# TX.net
KiCad netlist of a schematic drawn in Altium Designer
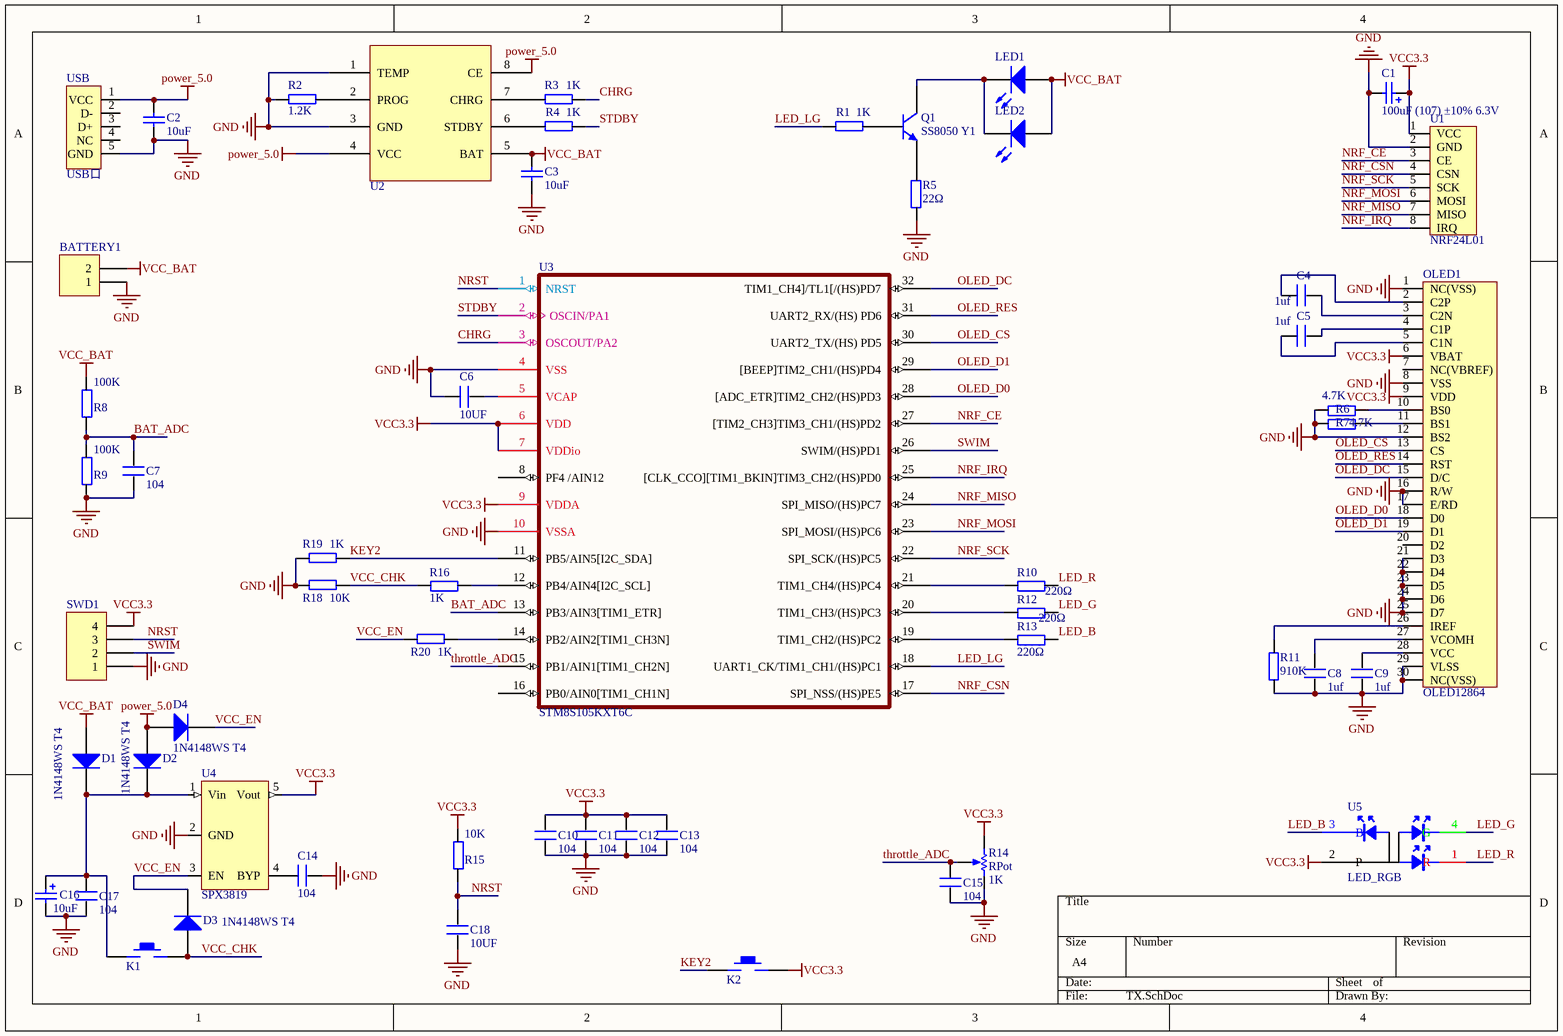
[diagram p0: TX.SchDoc]

(export (version "E")
  (design (tool "Eeschema 10.0.6"))
  (components
    (comp (ref "BATTERY1")
      (value "battery")
      (footprint "HDR1X2")
      (description "Header, 2-Pin")
      (fields (field (name "PUBLISHER") "Altium Limited"))
      (libsource (lib "EXPLORER") (part "Header 2"))
    )
    (comp (ref "C1")
      (value "100uF (107) ±10% 6.3V")
      (footprint "CASE-B_3528")
      (description "钽电容")
      (libsource (lib "Cap") (part "3528 100uF (107) 10% 6.3V"))
    )
    (comp (ref "C2")
      (value "10uF")
      (footprint "1206_C")
      (description "贴片电容")
      (libsource (lib "Cap") (part "1206 10uF (106) 10% 50V"))
    )
    (comp (ref "C3")
      (value "10uF")
      (footprint "1206_C")
      (description "贴片电容")
      (libsource (lib "Cap") (part "1206 10uF (106) 10% 50V"))
    )
    (comp (ref "C4") (value "1uf") (footprint "0603P") (libsource (lib "EXPLORER") (part "C")))
    (comp (ref "C5") (value "1uf") (footprint "0603P") (libsource (lib "EXPLORER") (part "C")))
    (comp (ref "C6") (value "10UF") (footprint "0805") (libsource (lib "EXPLORER") (part "C")))
    (comp (ref "C7") (value "104") (footprint "0603P") (libsource (lib "EXPLORER") (part "C")))
    (comp (ref "C8") (value "1uf") (footprint "0603P") (libsource (lib "EXPLORER") (part "C")))
    (comp (ref "C9") (value "1uf") (footprint "0603P") (libsource (lib "EXPLORER") (part "C")))
    (comp (ref "C10") (value "104") (footprint "0603P") (libsource (lib "EXPLORER") (part "C")))
    (comp (ref "C11") (value "104") (footprint "0603P") (libsource (lib "EXPLORER") (part "C")))
    (comp (ref "C12") (value "104") (footprint "0603P") (libsource (lib "EXPLORER") (part "C")))
    (comp (ref "C13") (value "104") (footprint "0603P") (libsource (lib "EXPLORER") (part "C")))
    (comp (ref "C14") (value "104") (footprint "0603P") (libsource (lib "EXPLORER") (part "C")))
    (comp (ref "C15") (value "104") (footprint "0603P") (libsource (lib "EXPLORER") (part "C")))
    (comp (ref "C16")
      (value "10uF")
      (footprint "CASE-A_3216")
      (description "钽电容")
      (libsource (lib "Cap") (part "3216 10uF (106) 10% 16V"))
    )
    (comp (ref "C17") (value "104") (footprint "0603P") (libsource (lib "EXPLORER") (part "C")))
    (comp (ref "C18") (value "10UF") (footprint "0603P") (libsource (lib "EXPLORER") (part "C")))
    (comp (ref "D1")
      (value "1N4148WS T4")
      (footprint "SOD-323")
      (description "二极管")
      (libsource (lib "Diode") (part "SOD-323 1N4148WS T4"))
    )
    (comp (ref "D2")
      (value "1N4148WS T4")
      (footprint "SOD-323")
      (description "二极管")
      (libsource (lib "Diode") (part "SOD-323 1N4148WS T4"))
    )
    (comp (ref "D3")
      (value "1N4148WS T4")
      (footprint "SOD-323")
      (description "二极管")
      (libsource (lib "Diode") (part "SOD-323 1N4148WS T4"))
    )
    (comp (ref "D4")
      (value "1N4148WS T4")
      (footprint "SOD-323")
      (description "二极管")
      (libsource (lib "Diode") (part "SOD-323 1N4148WS T4"))
    )
    (comp (ref "K1") (value "KEY") (footprint "侧贴按键") (libsource (lib "EXPLORER") (part "KEY_M")))
    (comp (ref "K2") (value "KEY") (footprint "侧贴按键") (libsource (lib "EXPLORER") (part "KEY_M")))
    (comp (ref "LED1")
      (value "LED")
      (footprint "DIODE_3*5.3")
      (description "Typical RED, GREEN, YELLOW, AMBER GaAs LED")
      (fields (field (name "PUBLISHER") "Altium Limited"))
      (libsource (lib "EXPLORER") (part "LED2"))
    )
    (comp (ref "LED2")
      (value "LED")
      (footprint "DIODE_3*5.3")
      (description "Typical RED, GREEN, YELLOW, AMBER GaAs LED")
      (fields (field (name "PUBLISHER") "Altium Limited"))
      (libsource (lib "EXPLORER") (part "LED2"))
    )
    (comp (ref "OLED1")
      (value "OLED12864")
      (footprint "OLED_0.96")
      (libsource (lib "0.96OLED_SCH") (part "OLED12864"))
    )
    (comp (ref "Q1")
      (value "SS8050 Y1")
      (footprint "SOT-23(SOT-23-3)")
      (description "三极管")
      (libsource (lib "Transistor_NPN") (part "SOT-23 SS8050 Y1"))
    )
    (comp (ref "R1") (value "1K") (footprint "0603P") (libsource (lib "*") (part "R")))
    (comp (ref "R2") (value "1.2K") (footprint "0603P") (libsource (lib "*") (part "R")))
    (comp (ref "R3") (value "1K") (footprint "0603P") (libsource (lib "*") (part "R")))
    (comp (ref "R4") (value "1K") (footprint "0603P") (libsource (lib "*") (part "R")))
    (comp (ref "R5") (value "22Ω") (footprint "0603P") (libsource (lib "*") (part "R")))
    (comp (ref "R6") (value "4.7K") (footprint "0603P") (libsource (lib "*") (part "R")))
    (comp (ref "R7") (value "4.7K") (footprint "0603P") (libsource (lib "*") (part "R")))
    (comp (ref "R8") (value "100K") (footprint "0603P") (libsource (lib "*") (part "R")))
    (comp (ref "R9") (value "100K") (footprint "0603P") (libsource (lib "*") (part "R")))
    (comp (ref "R10") (value "220Ω") (footprint "0603P") (libsource (lib "*") (part "R")))
    (comp (ref "R11") (value "910K") (footprint "0603P") (libsource (lib "*") (part "R")))
    (comp (ref "R12") (value "220Ω") (footprint "0603P") (libsource (lib "*") (part "R")))
    (comp (ref "R13") (value "220Ω") (footprint "0603P") (libsource (lib "*") (part "R")))
    (comp (ref "R14")
      (value "RPot")
      (footprint "R_variable")
      (description "Potentiometer")
      (fields (field (name "ALTIUM_VALUE") "1K") (field (name "PUBLISHER") "Altium Limited"))
      (libsource (lib "Miscellaneous Devices") (part "RPot"))
    )
    (comp (ref "R15") (value "10K") (footprint "0603P") (libsource (lib "*") (part "R")))
    (comp (ref "R16") (value "1K") (footprint "0603P") (libsource (lib "*") (part "R")))
    (comp (ref "R18") (value "10K") (footprint "0603P") (libsource (lib "*") (part "R")))
    (comp (ref "R19") (value "1K") (footprint "0603P") (libsource (lib "*") (part "R")))
    (comp (ref "R20") (value "1K") (footprint "0603P") (libsource (lib "*") (part "R")))
    (comp (ref "SWD1")
      (value "SWD")
      (footprint "HDR1X4")
      (description "Header, 4-Pin")
      (fields (field (name "PUBLISHER") "Altium Limited"))
      (libsource (lib "EXPLORER") (part "Header 4"))
    )
    (comp (ref "U1")
      (value "NRF24L01")
      (footprint "miniNRF24L01")
      (libsource (lib "MySchlib") (part "NRF24L01"))
    )
    (comp (ref "U2") (value "TP4056-SOT8") (footprint "SOP-8") (libsource (lib "*") (part "TP4056")))
    (comp (ref "U3")
      (value "STM8S105KXT6C")
      (footprint "TQFP32")
      (description "ST 8-bit  Microcontroller")
      (libsource (lib "STMicrocontroller 8") (part "STM8S105K4T6C"))
    )
    (comp (ref "U4") (value "SPX3819") (footprint "SOT25-5") (libsource (lib "*") (part "SPX3819")))
    (comp (ref "U5")
      (value "LED_RGB")
      (footprint "LED_RGB")
      (description "全彩LED")
      (libsource (lib "*") (part "LED_RGB"))
    )
    (comp (ref "USB") (value "USB口") (footprint "MICRO USB") (libsource (lib "MySchlib") (part "USB口")))
  )
  (nets
    (net (code "1") (name "/BAT_ADC") (class "Default")
      (node (ref "C7") (pin "2") (pintype "passive"))
      (node (ref "R8") (pin "1") (pintype "passive"))
      (node (ref "R9") (pin "2") (pintype "passive"))
      (node (ref "U3") (pin "13") (pinfunction "PB3/AIN3[TIM1_ETR]_13") (pintype "bidirectional"))
    )
    (net (code "2") (name "/CHRG") (class "Default")
      (node (ref "R3") (pin "1") (pintype "passive"))
      (node (ref "U3") (pin "3") (pinfunction "OSCOUT/PA2_3") (pintype "bidirectional"))
    )
    (net (code "3") (name "/KEY2") (class "Default")
      (node (ref "K2") (pin "1") (pinfunction "1_1") (pintype "passive"))
      (node (ref "R19") (pin "1") (pintype "passive"))
      (node (ref "U3") (pin "11") (pinfunction "PB5/AIN5[I2C_SDA]_11") (pintype "bidirectional"))
    )
    (net (code "4") (name "/LED_B") (class "Default")
      (node (ref "R13") (pin "2") (pintype "passive"))
      (node (ref "U5") (pin "3") (pinfunction "B_3") (pintype "passive"))
    )
    (net (code "5") (name "/LED_G") (class "Default")
      (node (ref "R12") (pin "2") (pintype "passive"))
      (node (ref "U5") (pin "4") (pinfunction "G_4") (pintype "passive"))
    )
    (net (code "6") (name "/LED_LG") (class "Default")
      (node (ref "R1") (pin "2") (pintype "passive"))
      (node (ref "U3") (pin "18") (pinfunction "UART1_CK/TIM1_CH1/(HS)PC1_18") (pintype "bidirectional"))
    )
    (net (code "7") (name "/LED_R") (class "Default")
      (node (ref "R10") (pin "2") (pintype "passive"))
      (node (ref "U5") (pin "1") (pinfunction "R_1") (pintype "passive"))
    )
    (net (code "8") (name "/NRF_CE") (class "Default")
      (node (ref "U1") (pin "3") (pinfunction "CE_3") (pintype "passive"))
      (node (ref "U3") (pin "27") (pinfunction "[TIM2_CH3]TIM3_CH1/(HS)PD2_27") (pintype "bidirectional"))
    )
    (net (code "9") (name "/NRF_CSN") (class "Default")
      (node (ref "U1") (pin "4") (pinfunction "CSN_4") (pintype "passive"))
      (node (ref "U3") (pin "17") (pinfunction "SPI_NSS/(HS)PE5_17") (pintype "bidirectional"))
    )
    (net (code "10") (name "/NRF_IRQ") (class "Default")
      (node (ref "U1") (pin "8") (pinfunction "IRQ_8") (pintype "passive"))
      (node (ref "U3") (pin "25") (pinfunction "[CLK_CCO][TIM1_BKIN]TIM3_CH2/(HS)PD0_25") (pintype "bidirectional"))
    )
    (net (code "11") (name "/NRF_MISO") (class "Default")
      (node (ref "U1") (pin "7") (pinfunction "MISO_7") (pintype "passive"))
      (node (ref "U3") (pin "24") (pinfunction "SPI_MISO/(HS)PC7_24") (pintype "bidirectional"))
    )
    (net (code "12") (name "/NRF_MOSI") (class "Default")
      (node (ref "U1") (pin "6") (pinfunction "MOSI_6") (pintype "passive"))
      (node (ref "U3") (pin "23") (pinfunction "SPI_MOSI/(HS)PC6_23") (pintype "bidirectional"))
    )
    (net (code "13") (name "/NRF_SCK") (class "Default")
      (node (ref "U1") (pin "5") (pinfunction "SCK_5") (pintype "passive"))
      (node (ref "U3") (pin "22") (pinfunction "SPI_SCK/(HS)PC5_22") (pintype "bidirectional"))
    )
    (net (code "14") (name "/NRST") (class "Default")
      (node (ref "C18") (pin "2") (pintype "passive"))
      (node (ref "R15") (pin "1") (pintype "passive"))
      (node (ref "SWD1") (pin "3") (pinfunction "3_3") (pintype "passive"))
      (node (ref "U3") (pin "1") (pinfunction "NRST_1") (pintype "bidirectional"))
    )
    (net (code "15") (name "/OLED_CS") (class "Default")
      (node (ref "OLED1") (pin "13") (pinfunction "CS_13") (pintype "passive"))
      (node (ref "U3") (pin "30") (pinfunction "UART2_TX/(HS)_PD5_30") (pintype "bidirectional"))
    )
    (net (code "16") (name "/OLED_D0") (class "Default")
      (node (ref "OLED1") (pin "18") (pinfunction "D0_18") (pintype "passive"))
      (node (ref "U3") (pin "28") (pinfunction "[ADC_ETR]TIM2_CH2/(HS)PD3_28") (pintype "bidirectional"))
    )
    (net (code "17") (name "/OLED_D1") (class "Default")
      (node (ref "OLED1") (pin "19") (pinfunction "D1_19") (pintype "passive"))
      (node (ref "U3") (pin "29") (pinfunction "[BEEP]TIM2_CH1/(HS)PD4_29") (pintype "bidirectional"))
    )
    (net (code "18") (name "/OLED_DC") (class "Default")
      (node (ref "OLED1") (pin "15") (pinfunction "D/C_15") (pintype "passive"))
      (node (ref "U3") (pin "32") (pinfunction "TIM1_CH4]/TL1[/(HS)PD7_32") (pintype "bidirectional"))
    )
    (net (code "19") (name "/OLED_RES") (class "Default")
      (node (ref "OLED1") (pin "14") (pinfunction "RST_14") (pintype "passive"))
      (node (ref "U3") (pin "31") (pinfunction "UART2_RX/(HS)_PD6_31") (pintype "bidirectional"))
    )
    (net (code "20") (name "/STDBY") (class "Default")
      (node (ref "R4") (pin "1") (pintype "passive"))
      (node (ref "U3") (pin "2") (pinfunction "OSCIN/PA1_2") (pintype "bidirectional"))
    )
    (net (code "21") (name "/SWIM") (class "Default")
      (node (ref "SWD1") (pin "2") (pinfunction "2_2") (pintype "passive"))
      (node (ref "U3") (pin "26") (pinfunction "SWIM/(HS)PD1_26") (pintype "bidirectional"))
    )
    (net (code "22") (name "/VCC_CHK") (class "Default")
      (node (ref "D3") (pin "1") (pinfunction "A_1") (pintype "passive"))
      (node (ref "K1") (pin "2") (pinfunction "2_2") (pintype "passive"))
      (node (ref "R16") (pin "1") (pintype "passive"))
      (node (ref "R18") (pin "1") (pintype "passive"))
    )
    (net (code "23") (name "/VCC_EN") (class "Default")
      (node (ref "D3") (pin "2") (pinfunction "K_2") (pintype "passive"))
      (node (ref "D4") (pin "2") (pinfunction "K_2") (pintype "passive"))
      (node (ref "R20") (pin "2") (pintype "passive"))
      (node (ref "U4") (pin "3") (pinfunction "EN_3") (pintype "passive"))
    )
    (net (code "24") (name "/throttle_ADC") (class "Default")
      (node (ref "C15") (pin "2") (pintype "passive"))
      (node (ref "R14") (pin "3") (pinfunction "TAP_3") (pintype "passive"))
      (node (ref "U3") (pin "15") (pinfunction "PB1/AIN1[TIM1_CH2N]_15") (pintype "bidirectional"))
    )
    (net (code "25") (name "GND") (class "Default")
      (node (ref "BATTERY1") (pin "1") (pinfunction "1_1") (pintype "passive"))
      (node (ref "C1") (pin "2") (pinfunction "2_2") (pintype "passive"))
      (node (ref "C10") (pin "1") (pintype "passive"))
      (node (ref "C11") (pin "1") (pintype "passive"))
      (node (ref "C12") (pin "1") (pintype "passive"))
      (node (ref "C13") (pin "1") (pintype "passive"))
      (node (ref "C14") (pin "1") (pintype "passive"))
      (node (ref "C15") (pin "1") (pintype "passive"))
      (node (ref "C16") (pin "2") (pinfunction "2_2") (pintype "passive"))
      (node (ref "C17") (pin "1") (pintype "passive"))
      (node (ref "C18") (pin "1") (pintype "passive"))
      (node (ref "C2") (pin "1") (pinfunction "1_1") (pintype "passive"))
      (node (ref "C3") (pin "1") (pinfunction "1_1") (pintype "passive"))
      (node (ref "C6") (pin "2") (pintype "passive"))
      (node (ref "C7") (pin "1") (pintype "passive"))
      (node (ref "C8") (pin "1") (pintype "passive"))
      (node (ref "C9") (pin "1") (pintype "passive"))
      (node (ref "OLED1") (pin "1") (pinfunction "NC(VSS)_1") (pintype "passive"))
      (node (ref "OLED1") (pin "12") (pinfunction "BS2_12") (pintype "passive"))
      (node (ref "OLED1") (pin "16") (pinfunction "R/W_16") (pintype "passive"))
      (node (ref "OLED1") (pin "17") (pinfunction "E/RD_17") (pintype "passive"))
      (node (ref "OLED1") (pin "21") (pinfunction "D3_21") (pintype "passive"))
      (node (ref "OLED1") (pin "22") (pinfunction "D4_22") (pintype "passive"))
      (node (ref "OLED1") (pin "23") (pinfunction "D5_23") (pintype "passive"))
      (node (ref "OLED1") (pin "24") (pinfunction "D6_24") (pintype "passive"))
      (node (ref "OLED1") (pin "25") (pinfunction "D7_25") (pintype "passive"))
      (node (ref "OLED1") (pin "29") (pinfunction "VLSS_29") (pintype "passive"))
      (node (ref "OLED1") (pin "30") (pinfunction "NC(VSS)_30") (pintype "passive"))
      (node (ref "OLED1") (pin "8") (pinfunction "VSS_8") (pintype "passive"))
      (node (ref "R11") (pin "2") (pintype "passive"))
      (node (ref "R14") (pin "2") (pinfunction "BOT_2") (pintype "passive"))
      (node (ref "R18") (pin "2") (pintype "passive"))
      (node (ref "R19") (pin "2") (pintype "passive"))
      (node (ref "R2") (pin "2") (pintype "passive"))
      (node (ref "R5") (pin "2") (pintype "passive"))
      (node (ref "R6") (pin "1") (pintype "passive"))
      (node (ref "R7") (pin "1") (pintype "passive"))
      (node (ref "R9") (pin "1") (pintype "passive"))
      (node (ref "SWD1") (pin "1") (pinfunction "1_1") (pintype "passive"))
      (node (ref "U1") (pin "2") (pinfunction "GND_2") (pintype "passive"))
      (node (ref "U2") (pin "1") (pinfunction "TEMP_1") (pintype "passive"))
      (node (ref "U2") (pin "3") (pinfunction "GND_3") (pintype "passive"))
      (node (ref "U3") (pin "10") (pinfunction "VSSA_10") (pintype "power_in"))
      (node (ref "U3") (pin "4") (pinfunction "VSS_4") (pintype "power_in"))
      (node (ref "U4") (pin "2") (pinfunction "GND_2") (pintype "passive"))
      (node (ref "USB") (pin "5") (pinfunction "GND_5") (pintype "passive"))
    )
    (net (code "26") (name "Net-(D1-K)") (class "Default")
      (node (ref "C16") (pin "1") (pinfunction "1_1") (pintype "passive"))
      (node (ref "C17") (pin "2") (pintype "passive"))
      (node (ref "D1") (pin "2") (pinfunction "K_2") (pintype "passive"))
      (node (ref "D2") (pin "2") (pinfunction "K_2") (pintype "passive"))
      (node (ref "K1") (pin "1") (pinfunction "1_1") (pintype "passive"))
      (node (ref "U4") (pin "1") (pinfunction "Vin_1") (pintype "input"))
    )
    (net (code "27") (name "Net-(LED1-K)") (class "Default")
      (node (ref "LED1") (pin "2") (pinfunction "K_2") (pintype "passive"))
      (node (ref "LED2") (pin "2") (pinfunction "K_2") (pintype "passive"))
      (node (ref "Q1") (pin "3") (pinfunction "C_3") (pintype "passive"))
    )
    (net (code "28") (name "Net-(OLED1-BS0)") (class "Default")
      (node (ref "OLED1") (pin "10") (pinfunction "BS0_10") (pintype "passive"))
      (node (ref "R6") (pin "2") (pintype "passive"))
    )
    (net (code "29") (name "Net-(OLED1-BS1)") (class "Default")
      (node (ref "OLED1") (pin "11") (pinfunction "BS1_11") (pintype "passive"))
      (node (ref "R7") (pin "2") (pintype "passive"))
    )
    (net (code "30") (name "Net-(OLED1-C1N)") (class "Default")
      (node (ref "C5") (pin "1") (pintype "passive"))
      (node (ref "OLED1") (pin "5") (pinfunction "C1N_5") (pintype "passive"))
    )
    (net (code "31") (name "Net-(OLED1-C1P)") (class "Default")
      (node (ref "C5") (pin "2") (pintype "passive"))
      (node (ref "OLED1") (pin "4") (pinfunction "C1P_4") (pintype "passive"))
    )
    (net (code "32") (name "Net-(OLED1-C2N)") (class "Default")
      (node (ref "C4") (pin "2") (pintype "passive"))
      (node (ref "OLED1") (pin "3") (pinfunction "C2N_3") (pintype "passive"))
    )
    (net (code "33") (name "Net-(OLED1-C2P)") (class "Default")
      (node (ref "C4") (pin "1") (pintype "passive"))
      (node (ref "OLED1") (pin "2") (pinfunction "C2P_2") (pintype "passive"))
    )
    (net (code "34") (name "Net-(OLED1-IREF)") (class "Default")
      (node (ref "OLED1") (pin "26") (pinfunction "IREF_26") (pintype "passive"))
      (node (ref "R11") (pin "1") (pintype "passive"))
    )
    (net (code "35") (name "Net-(OLED1-VCC)") (class "Default")
      (node (ref "C9") (pin "2") (pintype "passive"))
      (node (ref "OLED1") (pin "28") (pinfunction "VCC_28") (pintype "passive"))
    )
    (net (code "36") (name "Net-(OLED1-VCOMH)") (class "Default")
      (node (ref "C8") (pin "2") (pintype "passive"))
      (node (ref "OLED1") (pin "27") (pinfunction "VCOMH_27") (pintype "passive"))
    )
    (net (code "37") (name "Net-(Q1-B)") (class "Default")
      (node (ref "Q1") (pin "1") (pinfunction "B_1") (pintype "passive"))
      (node (ref "R1") (pin "1") (pintype "passive"))
    )
    (net (code "38") (name "Net-(Q1-E)") (class "Default")
      (node (ref "Q1") (pin "2") (pinfunction "E_2") (pintype "passive"))
      (node (ref "R5") (pin "1") (pintype "passive"))
    )
    (net (code "39") (name "Net-(U2-CHRG)") (class "Default")
      (node (ref "R3") (pin "2") (pintype "passive"))
      (node (ref "U2") (pin "7") (pinfunction "CHRG_7") (pintype "passive"))
    )
    (net (code "40") (name "Net-(U2-PROG)") (class "Default")
      (node (ref "R2") (pin "1") (pintype "passive"))
      (node (ref "U2") (pin "2") (pinfunction "PROG_2") (pintype "passive"))
    )
    (net (code "41") (name "Net-(U2-STDBY)") (class "Default")
      (node (ref "R4") (pin "2") (pintype "passive"))
      (node (ref "U2") (pin "6") (pinfunction "STDBY_6") (pintype "passive"))
    )
    (net (code "42") (name "Net-(U3-PB2{slash}AIN2[TIM1_CH3N])") (class "Default")
      (node (ref "R20") (pin "1") (pintype "passive"))
      (node (ref "U3") (pin "14") (pinfunction "PB2/AIN2[TIM1_CH3N]_14") (pintype "bidirectional"))
    )
    (net (code "43") (name "Net-(U3-PB4{slash}AIN4[I2C_SCL])") (class "Default")
      (node (ref "R16") (pin "2") (pintype "passive"))
      (node (ref "U3") (pin "12") (pinfunction "PB4/AIN4[I2C_SCL]_12") (pintype "bidirectional"))
    )
    (net (code "44") (name "Net-(U3-TIM1_CH2{slash}(HS)PC2)") (class "Default")
      (node (ref "R13") (pin "1") (pintype "passive"))
      (node (ref "U3") (pin "19") (pinfunction "TIM1_CH2/(HS)PC2_19") (pintype "bidirectional"))
    )
    (net (code "45") (name "Net-(U3-TIM1_CH3{slash}(HS)PC3)") (class "Default")
      (node (ref "R12") (pin "1") (pintype "passive"))
      (node (ref "U3") (pin "20") (pinfunction "TIM1_CH3/(HS)PC3_20") (pintype "bidirectional"))
    )
    (net (code "46") (name "Net-(U3-TIM1_CH4{slash}(HS)PC4)") (class "Default")
      (node (ref "R10") (pin "1") (pintype "passive"))
      (node (ref "U3") (pin "21") (pinfunction "TIM1_CH4/(HS)PC4_21") (pintype "bidirectional"))
    )
    (net (code "47") (name "Net-(U3-VCAP)") (class "Default")
      (node (ref "C6") (pin "1") (pintype "passive"))
      (node (ref "U3") (pin "5") (pinfunction "VCAP_5") (pintype "power_in"))
    )
    (net (code "48") (name "Net-(U4-BYP)") (class "Default")
      (node (ref "C14") (pin "2") (pintype "passive"))
      (node (ref "U4") (pin "4") (pinfunction "BYP_4") (pintype "passive"))
    )
    (net (code "49") (name "VCC3.3") (class "Default")
      (node (ref "C1") (pin "1") (pinfunction "1_1") (pintype "passive"))
      (node (ref "C10") (pin "2") (pintype "passive"))
      (node (ref "C11") (pin "2") (pintype "passive"))
      (node (ref "C12") (pin "2") (pintype "passive"))
      (node (ref "C13") (pin "2") (pintype "passive"))
      (node (ref "K2") (pin "2") (pinfunction "2_2") (pintype "passive"))
      (node (ref "OLED1") (pin "6") (pinfunction "VBAT_6") (pintype "passive"))
      (node (ref "OLED1") (pin "9") (pinfunction "VDD_9") (pintype "passive"))
      (node (ref "R14") (pin "1") (pinfunction "TOP_1") (pintype "passive"))
      (node (ref "R15") (pin "2") (pintype "passive"))
      (node (ref "SWD1") (pin "4") (pinfunction "4_4") (pintype "passive"))
      (node (ref "U1") (pin "1") (pinfunction "VCC_1") (pintype "passive"))
      (node (ref "U3") (pin "6") (pinfunction "VDD_6") (pintype "power_in"))
      (node (ref "U3") (pin "7") (pinfunction "VDDio_7") (pintype "power_in"))
      (node (ref "U3") (pin "9") (pinfunction "VDDA_9") (pintype "power_in"))
      (node (ref "U4") (pin "5") (pinfunction "Vout_5") (pintype "output"))
      (node (ref "U5") (pin "2") (pinfunction "P_2") (pintype "passive"))
    )
    (net (code "50") (name "VCC_BAT") (class "Default")
      (node (ref "BATTERY1") (pin "2") (pinfunction "2_2") (pintype "passive"))
      (node (ref "C3") (pin "2") (pinfunction "2_2") (pintype "passive"))
      (node (ref "D1") (pin "1") (pinfunction "A_1") (pintype "passive"))
      (node (ref "LED1") (pin "1") (pinfunction "A_1") (pintype "passive"))
      (node (ref "LED2") (pin "1") (pinfunction "A_1") (pintype "passive"))
      (node (ref "R8") (pin "2") (pintype "passive"))
      (node (ref "U2") (pin "5") (pinfunction "BAT_5") (pintype "passive"))
    )
    (net (code "51") (name "power_5.0") (class "Default")
      (node (ref "C2") (pin "2") (pinfunction "2_2") (pintype "passive"))
      (node (ref "D2") (pin "1") (pinfunction "A_1") (pintype "passive"))
      (node (ref "D4") (pin "1") (pinfunction "A_1") (pintype "passive"))
      (node (ref "U2") (pin "4") (pinfunction "VCC_4") (pintype "passive"))
      (node (ref "U2") (pin "8") (pinfunction "CE_8") (pintype "passive"))
      (node (ref "USB") (pin "1") (pinfunction "VCC_1") (pintype "passive"))
    )
    (net (code "52") (name "unconnected-(OLED1-D2-Pad20)") (class "Default")
      (node (ref "OLED1") (pin "20") (pinfunction "D2_20") (pintype "passive"))
    )
    (net (code "53") (name "unconnected-(OLED1-NC(VBREF)-Pad7)") (class "Default")
      (node (ref "OLED1") (pin "7") (pinfunction "NC(VBREF)_7") (pintype "passive"))
    )
    (net (code "54") (name "unconnected-(U3-PB0{slash}AIN0[TIM1_CH1N]-Pad16)") (class "Default")
      (node (ref "U3") (pin "16") (pinfunction "PB0/AIN0[TIM1_CH1N]_16") (pintype "bidirectional"))
    )
    (net (code "55") (name "unconnected-(U3-PF4_{slash}AIN12-Pad8)") (class "Default")
      (node (ref "U3") (pin "8") (pinfunction "PF4_/AIN12_8") (pintype "bidirectional"))
    )
    (net (code "56") (name "unconnected-(USB-D+-Pad3)") (class "Default")
      (node (ref "USB") (pin "3") (pinfunction "D+_3") (pintype "passive"))
    )
    (net (code "57") (name "unconnected-(USB-D--Pad2)") (class "Default")
      (node (ref "USB") (pin "2") (pinfunction "D-_2") (pintype "passive"))
    )
    (net (code "58") (name "unconnected-(USB-NC-Pad4)") (class "Default")
      (node (ref "USB") (pin "4") (pinfunction "NC_4") (pintype "passive"))
    )
  )
)
